# BPDC_mid.net
KiCad netlist of a schematic drawn in Altium Designer
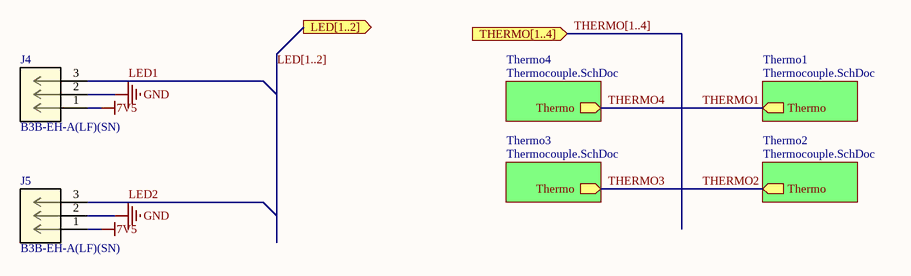
[diagram p0: BPDC mid.SchDoc]

(export (version "E")
  (design (tool "Eeschema 10.0.6"))
  (components
    (comp (ref "J4")
      (value "B3B-EH-A(LF)(SN)")
      (footprint "CONN3_B3B-EH-A(LF)(SN)_JST")
      (description "No Description Available")
      (fields (field (name "COPYRIGHT") "Copyright (C) 2018 Accelerated Designs. All rights reserved"))
      (libsource (lib "2020-10-15_19-17-05") (part "B3B-EH-A(LF)(SN)"))
    )
    (comp (ref "J5")
      (value "B3B-EH-A(LF)(SN)")
      (footprint "CONN3_B3B-EH-A(LF)(SN)_JST")
      (description "No Description Available")
      (fields (field (name "COPYRIGHT") "Copyright (C) 2018 Accelerated Designs. All rights reserved"))
      (libsource (lib "2020-10-15_19-17-05") (part "B3B-EH-A(LF)(SN)"))
    )
  )
  (nets
    (net (code "1") (name "/LED1") (class "Default")
      (node (ref "J4") (pin "3") (pinfunction "3_3") (pintype "passive"))
    )
    (net (code "2") (name "/LED2") (class "Default")
      (node (ref "J5") (pin "3") (pinfunction "3_3") (pintype "passive"))
    )
    (net (code "6") (name "7V5") (class "Default")
      (node (ref "J4") (pin "1") (pinfunction "1_1") (pintype "passive"))
      (node (ref "J5") (pin "1") (pinfunction "1_1") (pintype "passive"))
    )
    (net (code "7") (name "GND") (class "Default")
      (node (ref "J4") (pin "2") (pinfunction "2_2") (pintype "passive"))
      (node (ref "J5") (pin "2") (pinfunction "2_2") (pintype "passive"))
    )
  )
)
